# IRBlaster.net
KiCad netlist of a schematic drawn in EAGLE
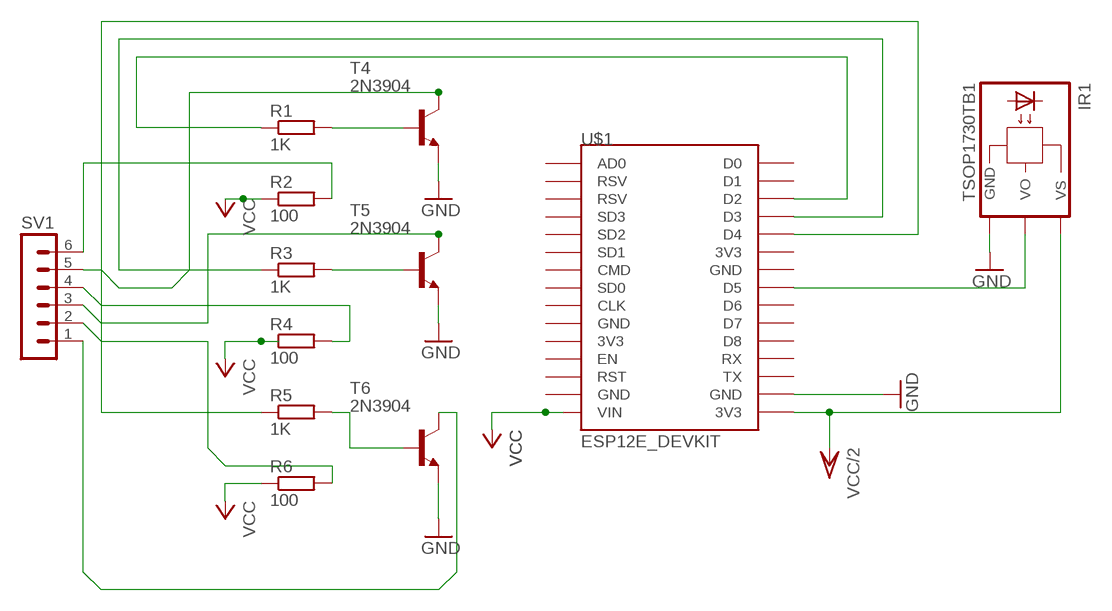
[diagram p0: schematic, sheet 1]

(export (version "E")
  (design (tool "Eeschema 10.0.6"))
  (components
    (comp (ref "IR1")
      (value "TSOP1730TB1")
      (footprint "eagle-import:TSOP17_TB1")
      (libsource (lib "eagle-import") (part "TSOP17TB130"))
    )
    (comp (ref "R1")
      (value "1K")
      (footprint "eagle-import:0207_10")
      (libsource (lib "eagle-import") (part "R-EU_0207/10"))
    )
    (comp (ref "R2")
      (value "100")
      (footprint "eagle-import:0207_10")
      (libsource (lib "eagle-import") (part "R-EU_0207/10"))
    )
    (comp (ref "R3")
      (value "1K")
      (footprint "eagle-import:0207_10")
      (libsource (lib "eagle-import") (part "R-EU_0207/10"))
    )
    (comp (ref "R4")
      (value "100")
      (footprint "eagle-import:0207_10")
      (libsource (lib "eagle-import") (part "R-EU_0207/10"))
    )
    (comp (ref "R5")
      (value "1K")
      (footprint "eagle-import:0207_10")
      (libsource (lib "eagle-import") (part "R-EU_0207/10"))
    )
    (comp (ref "R6")
      (value "100")
      (footprint "eagle-import:0207_10")
      (libsource (lib "eagle-import") (part "R-EU_0207/10"))
    )
    (comp (ref "SV1")
      (value "MA06-1")
      (footprint "eagle-import:MA06-1")
      (libsource (lib "eagle-import") (part "MA06-1"))
    )
    (comp (ref "T4")
      (value "2N3904")
      (footprint "eagle-import:TO92")
      (libsource (lib "eagle-import") (part "2N3904"))
    )
    (comp (ref "T5")
      (value "2N3904")
      (footprint "eagle-import:TO92")
      (libsource (lib "eagle-import") (part "2N3904"))
    )
    (comp (ref "T6")
      (value "2N3904")
      (footprint "eagle-import:TO92")
      (libsource (lib "eagle-import") (part "2N3904"))
    )
    (comp (ref "U$1")
      (value "ESP12E_DEVKIT")
      (footprint "eagle-import:ESP12E_DEVKIT")
      (libsource (lib "eagle-import") (part "ESP12E_DEVKIT"))
    )
  )
  (nets
    (net (code "1") (name "GND") (class "Default")
      (node (ref "IR1") (pin "GND") (pinfunction "GND_GND") (pintype "power_in"))
      (node (ref "T4") (pin "3") (pinfunction "E_3") (pintype "passive"))
      (node (ref "T5") (pin "3") (pinfunction "E_3") (pintype "passive"))
      (node (ref "T6") (pin "3") (pinfunction "E_3") (pintype "passive"))
      (node (ref "U$1") (pin "GND@3") (pinfunction "GND_GND@3") (pintype "bidirectional"))
    )
    (net (code "2") (name "Net-(IR1-PadVO)") (class "Default")
      (node (ref "IR1") (pin "VO") (pinfunction "VO_VO") (pintype "open_collector"))
      (node (ref "U$1") (pin "D5") (pinfunction "D5_D5") (pintype "bidirectional"))
    )
    (net (code "3") (name "Net-(R1-Pad1)") (class "Default")
      (node (ref "R1") (pin "1") (pinfunction "1_1") (pintype "passive"))
      (node (ref "U$1") (pin "D2") (pinfunction "D2_D2") (pintype "bidirectional"))
    )
    (net (code "4") (name "Net-(R2-Pad2)") (class "Default")
      (node (ref "R2") (pin "2") (pinfunction "2_2") (pintype "passive"))
      (node (ref "SV1") (pin "6") (pinfunction "6_6") (pintype "passive"))
    )
    (net (code "5") (name "Net-(R3-Pad1)") (class "Default")
      (node (ref "R3") (pin "1") (pinfunction "1_1") (pintype "passive"))
      (node (ref "U$1") (pin "D3") (pinfunction "D3_D3") (pintype "bidirectional"))
    )
    (net (code "6") (name "Net-(R4-Pad2)") (class "Default")
      (node (ref "R4") (pin "2") (pinfunction "2_2") (pintype "passive"))
      (node (ref "SV1") (pin "4") (pinfunction "4_4") (pintype "passive"))
    )
    (net (code "7") (name "Net-(R5-Pad1)") (class "Default")
      (node (ref "R5") (pin "1") (pinfunction "1_1") (pintype "passive"))
      (node (ref "R6") (pin "2") (pinfunction "2_2") (pintype "passive"))
      (node (ref "SV1") (pin "2") (pinfunction "2_2") (pintype "passive"))
      (node (ref "U$1") (pin "D4") (pinfunction "D4_D4") (pintype "bidirectional"))
    )
    (net (code "8") (name "Net-(T4-B)") (class "Default")
      (node (ref "R1") (pin "2") (pinfunction "2_2") (pintype "passive"))
      (node (ref "T4") (pin "2") (pinfunction "B_2") (pintype "passive"))
    )
    (net (code "9") (name "Net-(T4-C)") (class "Default")
      (node (ref "SV1") (pin "5") (pinfunction "5_5") (pintype "passive"))
      (node (ref "T4") (pin "1") (pinfunction "C_1") (pintype "passive"))
    )
    (net (code "10") (name "Net-(T5-B)") (class "Default")
      (node (ref "R3") (pin "2") (pinfunction "2_2") (pintype "passive"))
      (node (ref "T5") (pin "2") (pinfunction "B_2") (pintype "passive"))
    )
    (net (code "11") (name "Net-(T5-C)") (class "Default")
      (node (ref "SV1") (pin "3") (pinfunction "3_3") (pintype "passive"))
      (node (ref "T5") (pin "1") (pinfunction "C_1") (pintype "passive"))
    )
    (net (code "12") (name "Net-(T6-B)") (class "Default")
      (node (ref "R5") (pin "2") (pinfunction "2_2") (pintype "passive"))
      (node (ref "T6") (pin "2") (pinfunction "B_2") (pintype "passive"))
    )
    (net (code "13") (name "Net-(T6-C)") (class "Default")
      (node (ref "SV1") (pin "1") (pinfunction "1_1") (pintype "passive"))
      (node (ref "T6") (pin "1") (pinfunction "C_1") (pintype "passive"))
    )
    (net (code "14") (name "VCC") (class "Default")
      (node (ref "R2") (pin "1") (pinfunction "1_1") (pintype "passive"))
      (node (ref "R4") (pin "1") (pinfunction "1_1") (pintype "passive"))
      (node (ref "R6") (pin "1") (pinfunction "1_1") (pintype "passive"))
      (node (ref "U$1") (pin "VIN") (pinfunction "VIN_VIN") (pintype "bidirectional"))
    )
    (net (code "15") (name "VCC{slash}2") (class "Default")
      (node (ref "IR1") (pin "VS") (pinfunction "VS_VS") (pintype "power_in"))
      (node (ref "U$1") (pin "3V3@2") (pinfunction "3V3_3V3@2") (pintype "bidirectional"))
    )
    (net (code "16") (name "unconnected-(U$1-3V3-Pad3V3@0)") (class "Default")
      (node (ref "U$1") (pin "3V3@0") (pinfunction "3V3_3V3@0") (pintype "bidirectional"))
    )
    (net (code "17") (name "unconnected-(U$1-3V3-Pad3V3@1)") (class "Default")
      (node (ref "U$1") (pin "3V3@1") (pinfunction "3V3_3V3@1") (pintype "bidirectional"))
    )
    (net (code "18") (name "unconnected-(U$1-GND-PadGND@0)") (class "Default")
      (node (ref "U$1") (pin "GND@0") (pinfunction "GND_GND@0") (pintype "bidirectional"))
    )
    (net (code "19") (name "unconnected-(U$1-GND-PadGND@1)") (class "Default")
      (node (ref "U$1") (pin "GND@1") (pinfunction "GND_GND@1") (pintype "bidirectional"))
    )
    (net (code "20") (name "unconnected-(U$1-GND-PadGND@2)") (class "Default")
      (node (ref "U$1") (pin "GND@2") (pinfunction "GND_GND@2") (pintype "bidirectional"))
    )
    (net (code "21") (name "unconnected-(U$1-PadAD0)") (class "Default")
      (node (ref "U$1") (pin "AD0") (pinfunction "AD0_AD0") (pintype "bidirectional"))
    )
    (net (code "22") (name "unconnected-(U$1-PadCLK)") (class "Default")
      (node (ref "U$1") (pin "CLK") (pinfunction "CLK_CLK") (pintype "bidirectional"))
    )
    (net (code "23") (name "unconnected-(U$1-PadCMD)") (class "Default")
      (node (ref "U$1") (pin "CMD") (pinfunction "CMD_CMD") (pintype "bidirectional"))
    )
    (net (code "24") (name "unconnected-(U$1-PadD0)") (class "Default")
      (node (ref "U$1") (pin "D0") (pinfunction "D0_D0") (pintype "bidirectional"))
    )
    (net (code "25") (name "unconnected-(U$1-PadD1)") (class "Default")
      (node (ref "U$1") (pin "D1") (pinfunction "D1_D1") (pintype "bidirectional"))
    )
    (net (code "26") (name "unconnected-(U$1-PadD6)") (class "Default")
      (node (ref "U$1") (pin "D6") (pinfunction "D6_D6") (pintype "bidirectional"))
    )
    (net (code "27") (name "unconnected-(U$1-PadD7)") (class "Default")
      (node (ref "U$1") (pin "D7") (pinfunction "D7_D7") (pintype "bidirectional"))
    )
    (net (code "28") (name "unconnected-(U$1-PadD8)") (class "Default")
      (node (ref "U$1") (pin "D8") (pinfunction "D8_D8") (pintype "bidirectional"))
    )
    (net (code "29") (name "unconnected-(U$1-PadEN)") (class "Default")
      (node (ref "U$1") (pin "EN") (pinfunction "EN_EN") (pintype "bidirectional"))
    )
    (net (code "30") (name "unconnected-(U$1-PadRST)") (class "Default")
      (node (ref "U$1") (pin "RST") (pinfunction "RST_RST") (pintype "bidirectional"))
    )
    (net (code "31") (name "unconnected-(U$1-PadRX)") (class "Default")
      (node (ref "U$1") (pin "RX") (pinfunction "RX_RX") (pintype "bidirectional"))
    )
    (net (code "32") (name "unconnected-(U$1-PadSD0)") (class "Default")
      (node (ref "U$1") (pin "SD0") (pinfunction "SD0_SD0") (pintype "bidirectional"))
    )
    (net (code "33") (name "unconnected-(U$1-PadSD1)") (class "Default")
      (node (ref "U$1") (pin "SD1") (pinfunction "SD1_SD1") (pintype "bidirectional"))
    )
    (net (code "34") (name "unconnected-(U$1-PadSD2)") (class "Default")
      (node (ref "U$1") (pin "SD2") (pinfunction "SD2_SD2") (pintype "bidirectional"))
    )
    (net (code "35") (name "unconnected-(U$1-PadSD3)") (class "Default")
      (node (ref "U$1") (pin "SD3") (pinfunction "SD3_SD3") (pintype "bidirectional"))
    )
    (net (code "36") (name "unconnected-(U$1-PadTX)") (class "Default")
      (node (ref "U$1") (pin "TX") (pinfunction "TX_TX") (pintype "bidirectional"))
    )
    (net (code "37") (name "unconnected-(U$1-RSV-PadRSV@0)") (class "Default")
      (node (ref "U$1") (pin "RSV@0") (pinfunction "RSV_RSV@0") (pintype "bidirectional"))
    )
    (net (code "38") (name "unconnected-(U$1-RSV-PadRSV@1)") (class "Default")
      (node (ref "U$1") (pin "RSV@1") (pinfunction "RSV_RSV@1") (pintype "bidirectional"))
    )
  )
)
